# HIVE_BOARD_CLOCK_GEN.net
KiCad netlist of a schematic drawn in Altium Designer
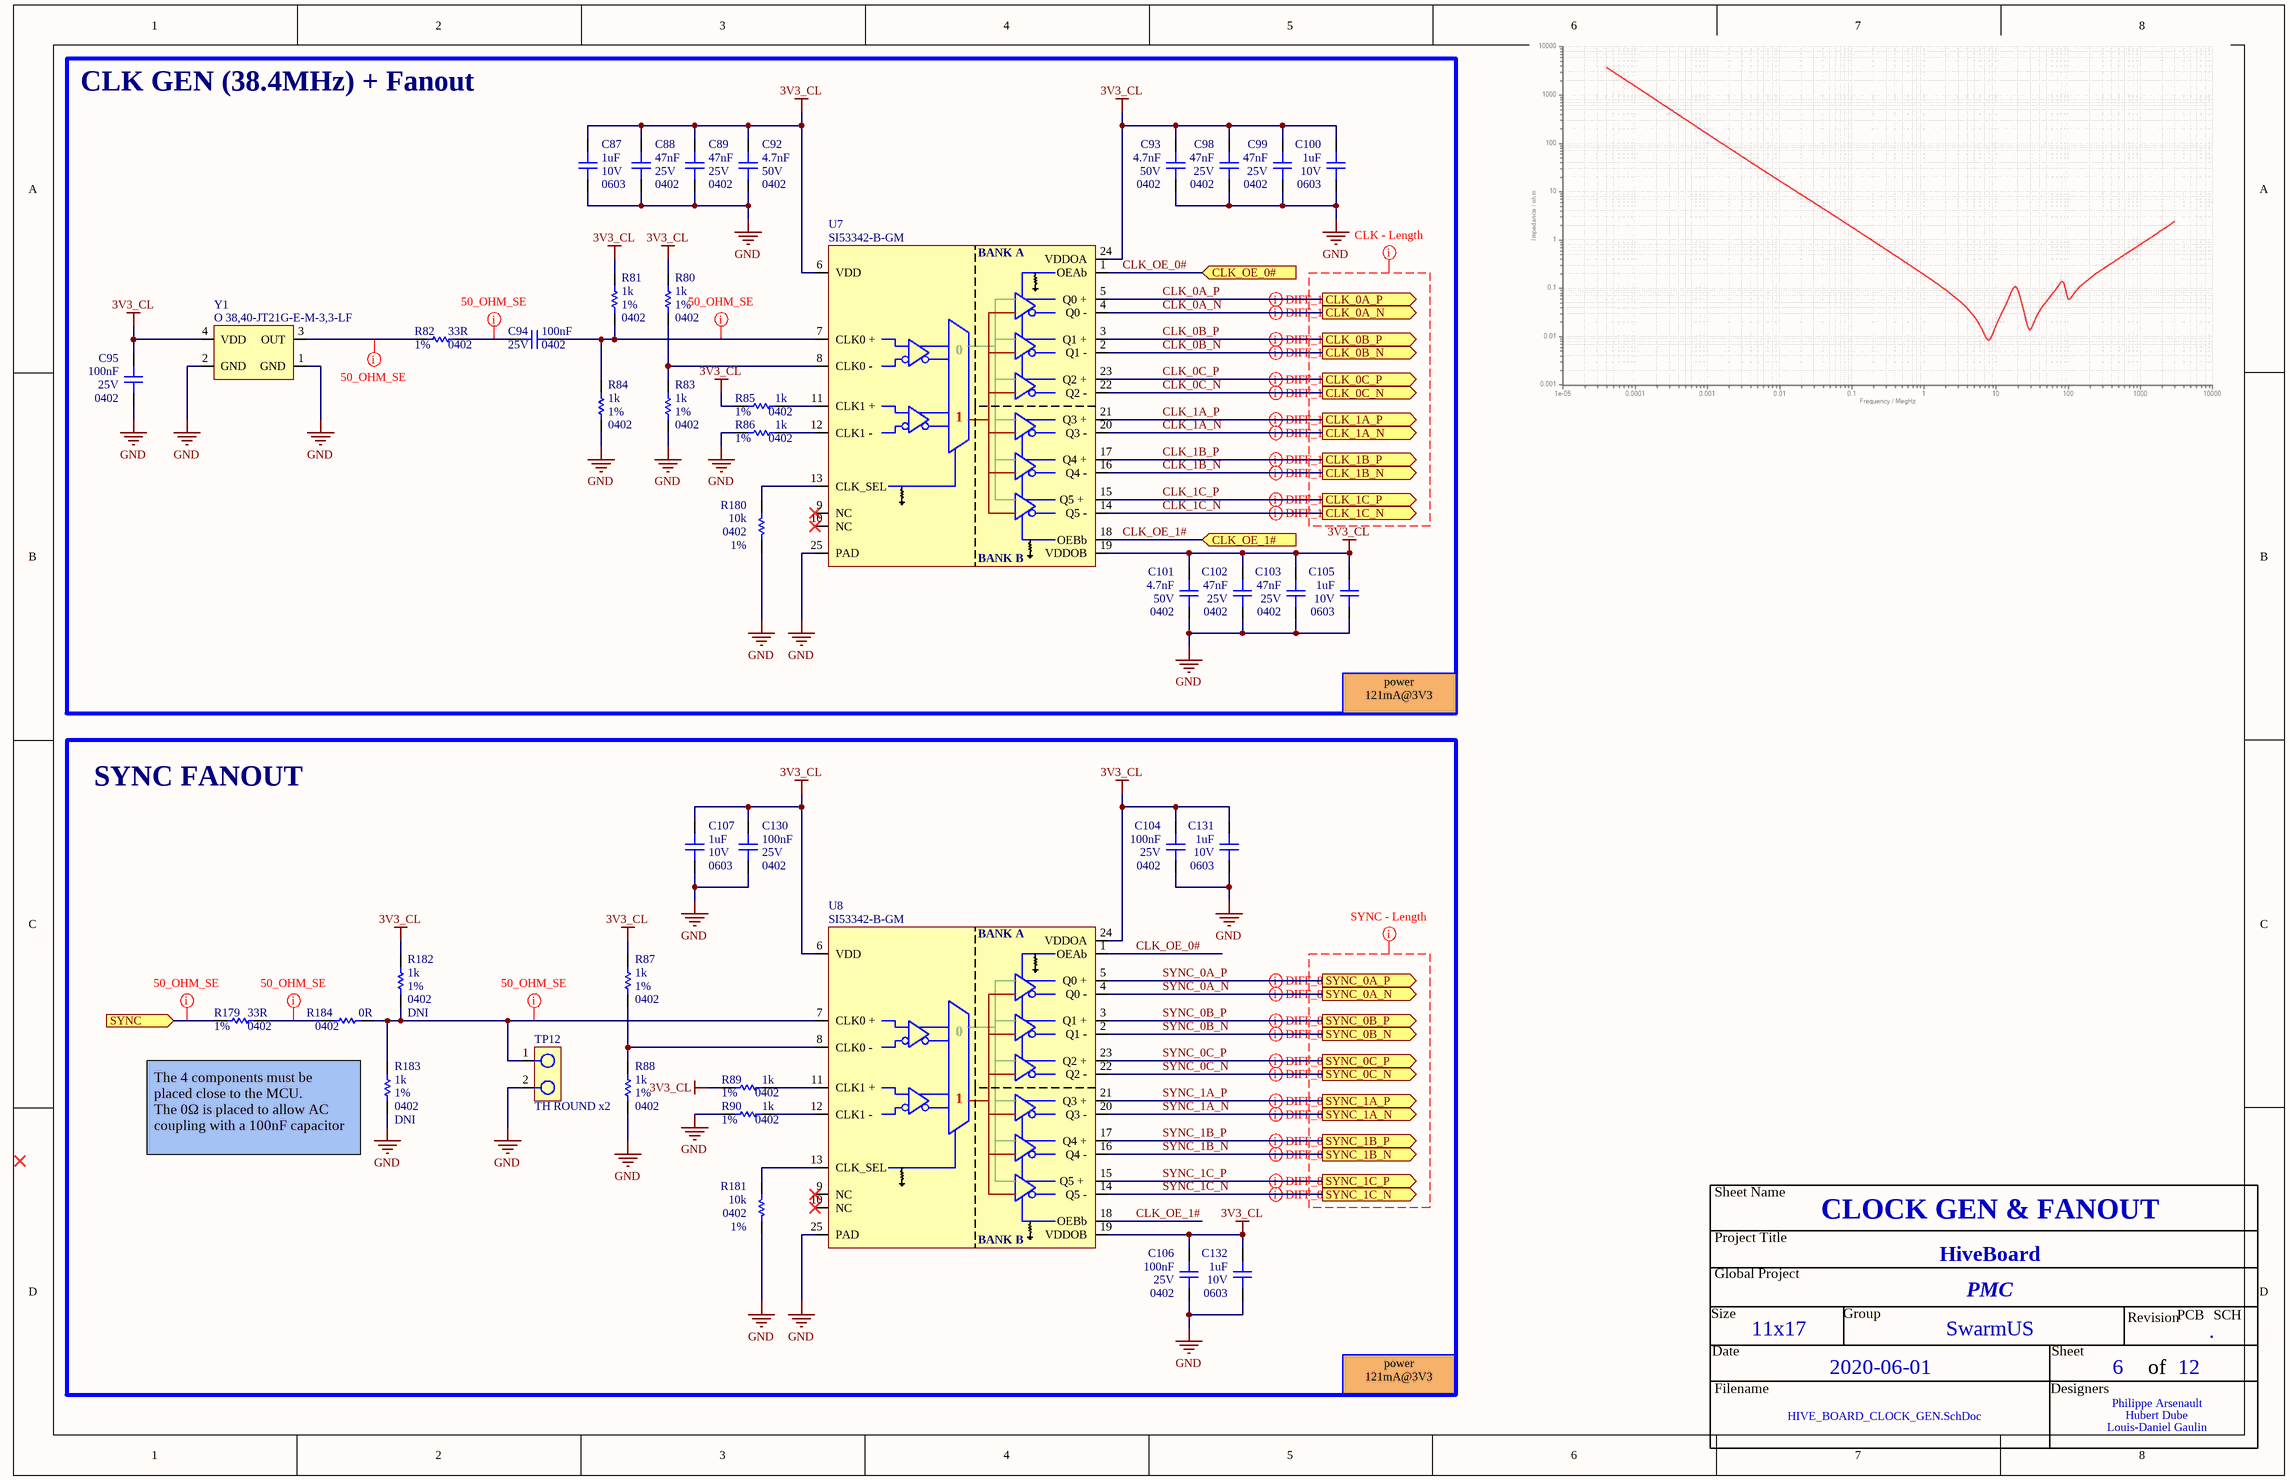
[diagram p0: HIVE_BOARD_CLOCK_GEN.SchDoc]

(export (version "E")
  (design (tool "Eeschema 10.0.6"))
  (components
    (comp (ref "C87")
      (value "1uF")
      (footprint "CAP_CER_0603")
      (description "CAP - CER 1uF 10V 10% X5R - 0603")
      (fields
        (field (name "TOLERANCE") "10%")
        (field (name "PACKAGE") "0603")
        (field (name "VOLTAGE RATING") "10V")
        (field (name "Comment") "C0603C105K8PACTU")
        (field (name "CREATEDBY/DATE") "Hubert Dube - 21/07/20")
        (field (name "VERIFIEDBY") "Louis-Daniel Gaulin - 21/07/20")
      )
      (libsource (lib "SWARMUS_LIB") (part "CAP_CER_C0603C105K8PACTU"))
    )
    (comp (ref "C88")
      (value "47nF")
      (footprint "CAP_CER_0402")
      (description "CAP - CER 47nF 25V X7R - 0402")
      (fields
        (field (name "TOLERANCE") "10%")
        (field (name "PACKAGE") "0402")
        (field (name "VOLTAGE RATING") "25V")
        (field (name "Comment") "GRM155R71E473KA88J")
        (field (name "CREATEDBY/DATE") "P. Marcoux 2020-02-05")
        (field (name "VERIFIEDBY") "C.Paulin - 22/04/2020")
      )
      (libsource (lib "GRAMS_MASTER_LIB") (part "CAP_CER_GRM155R71E473KA88J"))
    )
    (comp (ref "C89")
      (value "47nF")
      (footprint "CAP_CER_0402")
      (description "CAP - CER 47nF 25V X7R - 0402")
      (fields
        (field (name "TOLERANCE") "10%")
        (field (name "PACKAGE") "0402")
        (field (name "VOLTAGE RATING") "25V")
        (field (name "Comment") "GRM155R71E473KA88J")
        (field (name "CREATEDBY/DATE") "P. Marcoux 2020-02-05")
        (field (name "VERIFIEDBY") "C.Paulin - 22/04/2020")
      )
      (libsource (lib "GRAMS_MASTER_LIB") (part "CAP_CER_GRM155R71E473KA88J"))
    )
    (comp (ref "C92")
      (value "4.7nF")
      (footprint "CAP_CER_0402")
      (description "CAP - CER 4700PF 50V X7R 0402")
      (fields
        (field (name "TOLERANCE") "±10%")
        (field (name "PACKAGE") "0402")
        (field (name "VOLTAGE RATING") "50V")
        (field (name "Comment") "CL05B472KB5VPNC")
        (field (name "CREATEDBY/DATE") "Philippe Arsenault/ 2021-03-26")
      )
      (libsource (lib "SWARMUS_LIB") (part "CAP_CER_CL05B472KB5VPNC"))
    )
    (comp (ref "C93")
      (value "4.7nF")
      (footprint "CAP_CER_0402")
      (description "CAP - CER 4700PF 50V X7R 0402")
      (fields
        (field (name "TOLERANCE") "±10%")
        (field (name "PACKAGE") "0402")
        (field (name "VOLTAGE RATING") "50V")
        (field (name "Comment") "CL05B472KB5VPNC")
        (field (name "CREATEDBY/DATE") "Philippe Arsenault/ 2021-03-26")
      )
      (libsource (lib "SWARMUS_LIB") (part "CAP_CER_CL05B472KB5VPNC"))
    )
    (comp (ref "C94")
      (value "100nF")
      (footprint "CAP_CER_0402")
      (description "CAP - CER 0.1µF 10% 25V X7R - 0402")
      (fields
        (field (name "TOLERANCE") "10%")
        (field (name "PACKAGE") "0402")
        (field (name "VOLTAGE RATING") "25V")
        (field (name "Comment") "CGA2B3X7R1E104K050BB")
        (field (name "CREATEDBY/DATE") "Nicolas Roy 2018-11-07")
        (field (name "VERIFIEDBY") "Nicolas V. (2019-01-22)")
      )
      (libsource (lib "GRAMS_MASTER_LIB") (part "CAP_CER_CGA2B3X7R1E104K050BB"))
    )
    (comp (ref "C95")
      (value "100nF")
      (footprint "CAP_CER_0402")
      (description "CAP - CER 0.1µF 10% 25V X7R - 0402")
      (fields
        (field (name "TOLERANCE") "10%")
        (field (name "PACKAGE") "0402")
        (field (name "VOLTAGE RATING") "25V")
        (field (name "Comment") "CGA2B3X7R1E104K050BB")
        (field (name "CREATEDBY/DATE") "Nicolas Roy 2018-11-07")
        (field (name "VERIFIEDBY") "Nicolas V. (2019-01-22)")
      )
      (libsource (lib "GRAMS_MASTER_LIB") (part "CAP_CER_CGA2B3X7R1E104K050BB"))
    )
    (comp (ref "C98")
      (value "47nF")
      (footprint "CAP_CER_0402")
      (description "CAP - CER 47nF 25V X7R - 0402")
      (fields
        (field (name "TOLERANCE") "10%")
        (field (name "PACKAGE") "0402")
        (field (name "VOLTAGE RATING") "25V")
        (field (name "Comment") "GRM155R71E473KA88J")
        (field (name "CREATEDBY/DATE") "P. Marcoux 2020-02-05")
        (field (name "VERIFIEDBY") "C.Paulin - 22/04/2020")
      )
      (libsource (lib "GRAMS_MASTER_LIB") (part "CAP_CER_GRM155R71E473KA88J"))
    )
    (comp (ref "C99")
      (value "47nF")
      (footprint "CAP_CER_0402")
      (description "CAP - CER 47nF 25V X7R - 0402")
      (fields
        (field (name "TOLERANCE") "10%")
        (field (name "PACKAGE") "0402")
        (field (name "VOLTAGE RATING") "25V")
        (field (name "Comment") "GRM155R71E473KA88J")
        (field (name "CREATEDBY/DATE") "P. Marcoux 2020-02-05")
        (field (name "VERIFIEDBY") "C.Paulin - 22/04/2020")
      )
      (libsource (lib "GRAMS_MASTER_LIB") (part "CAP_CER_GRM155R71E473KA88J"))
    )
    (comp (ref "C100")
      (value "1uF")
      (footprint "CAP_CER_0603")
      (description "CAP - CER 1uF 10V 10% X5R - 0603")
      (fields
        (field (name "TOLERANCE") "10%")
        (field (name "PACKAGE") "0603")
        (field (name "VOLTAGE RATING") "10V")
        (field (name "Comment") "C0603C105K8PACTU")
        (field (name "CREATEDBY/DATE") "Hubert Dube - 21/07/20")
        (field (name "VERIFIEDBY") "Louis-Daniel Gaulin - 21/07/20")
      )
      (libsource (lib "SWARMUS_LIB") (part "CAP_CER_C0603C105K8PACTU"))
    )
    (comp (ref "C101")
      (value "4.7nF")
      (footprint "CAP_CER_0402")
      (description "CAP - CER 4700PF 50V X7R 0402")
      (fields
        (field (name "TOLERANCE") "±10%")
        (field (name "PACKAGE") "0402")
        (field (name "VOLTAGE RATING") "50V")
        (field (name "Comment") "CL05B472KB5VPNC")
        (field (name "CREATEDBY/DATE") "Philippe Arsenault/ 2021-03-26")
      )
      (libsource (lib "SWARMUS_LIB") (part "CAP_CER_CL05B472KB5VPNC"))
    )
    (comp (ref "C102")
      (value "47nF")
      (footprint "CAP_CER_0402")
      (description "CAP - CER 47nF 25V X7R - 0402")
      (fields
        (field (name "TOLERANCE") "10%")
        (field (name "PACKAGE") "0402")
        (field (name "VOLTAGE RATING") "25V")
        (field (name "Comment") "GRM155R71E473KA88J")
        (field (name "CREATEDBY/DATE") "P. Marcoux 2020-02-05")
        (field (name "VERIFIEDBY") "C.Paulin - 22/04/2020")
      )
      (libsource (lib "GRAMS_MASTER_LIB") (part "CAP_CER_GRM155R71E473KA88J"))
    )
    (comp (ref "C103")
      (value "47nF")
      (footprint "CAP_CER_0402")
      (description "CAP - CER 47nF 25V X7R - 0402")
      (fields
        (field (name "TOLERANCE") "10%")
        (field (name "PACKAGE") "0402")
        (field (name "VOLTAGE RATING") "25V")
        (field (name "Comment") "GRM155R71E473KA88J")
        (field (name "CREATEDBY/DATE") "P. Marcoux 2020-02-05")
        (field (name "VERIFIEDBY") "C.Paulin - 22/04/2020")
      )
      (libsource (lib "GRAMS_MASTER_LIB") (part "CAP_CER_GRM155R71E473KA88J"))
    )
    (comp (ref "C104")
      (value "100nF")
      (footprint "CAP_CER_0402")
      (description "CAP - CER 0.1µF 10% 25V X7R - 0402")
      (fields
        (field (name "TOLERANCE") "10%")
        (field (name "PACKAGE") "0402")
        (field (name "VOLTAGE RATING") "25V")
        (field (name "Comment") "CGA2B3X7R1E104K050BB")
        (field (name "CREATEDBY/DATE") "Nicolas Roy 2018-11-07")
        (field (name "VERIFIEDBY") "Nicolas V. (2019-01-22)")
      )
      (libsource (lib "GRAMS_MASTER_LIB") (part "CAP_CER_CGA2B3X7R1E104K050BB"))
    )
    (comp (ref "C105")
      (value "1uF")
      (footprint "CAP_CER_0603")
      (description "CAP - CER 1uF 10V 10% X5R - 0603")
      (fields
        (field (name "TOLERANCE") "10%")
        (field (name "PACKAGE") "0603")
        (field (name "VOLTAGE RATING") "10V")
        (field (name "Comment") "C0603C105K8PACTU")
        (field (name "CREATEDBY/DATE") "Hubert Dube - 21/07/20")
        (field (name "VERIFIEDBY") "Louis-Daniel Gaulin - 21/07/20")
      )
      (libsource (lib "SWARMUS_LIB") (part "CAP_CER_C0603C105K8PACTU"))
    )
    (comp (ref "C106")
      (value "100nF")
      (footprint "CAP_CER_0402")
      (description "CAP - CER 0.1µF 10% 25V X7R - 0402")
      (fields
        (field (name "TOLERANCE") "10%")
        (field (name "PACKAGE") "0402")
        (field (name "VOLTAGE RATING") "25V")
        (field (name "Comment") "CGA2B3X7R1E104K050BB")
        (field (name "CREATEDBY/DATE") "Nicolas Roy 2018-11-07")
        (field (name "VERIFIEDBY") "Nicolas V. (2019-01-22)")
      )
      (libsource (lib "GRAMS_MASTER_LIB") (part "CAP_CER_CGA2B3X7R1E104K050BB"))
    )
    (comp (ref "C107")
      (value "1uF")
      (footprint "CAP_CER_0603")
      (description "CAP - CER 1uF 10V 10% X5R - 0603")
      (fields
        (field (name "TOLERANCE") "10%")
        (field (name "PACKAGE") "0603")
        (field (name "VOLTAGE RATING") "10V")
        (field (name "Comment") "C0603C105K8PACTU")
        (field (name "CREATEDBY/DATE") "Hubert Dube - 21/07/20")
        (field (name "VERIFIEDBY") "Louis-Daniel Gaulin - 21/07/20")
      )
      (libsource (lib "SWARMUS_LIB") (part "CAP_CER_C0603C105K8PACTU"))
    )
    (comp (ref "C130")
      (value "100nF")
      (footprint "CAP_CER_0402")
      (description "CAP - CER 0.1µF 10% 25V X7R - 0402")
      (fields
        (field (name "TOLERANCE") "10%")
        (field (name "PACKAGE") "0402")
        (field (name "VOLTAGE RATING") "25V")
        (field (name "Comment") "CGA2B3X7R1E104K050BB")
        (field (name "CREATEDBY/DATE") "Nicolas Roy 2018-11-07")
        (field (name "VERIFIEDBY") "Nicolas V. (2019-01-22)")
      )
      (libsource (lib "GRAMS_MASTER_LIB") (part "CAP_CER_CGA2B3X7R1E104K050BB"))
    )
    (comp (ref "C131")
      (value "1uF")
      (footprint "CAP_CER_0603")
      (description "CAP - CER 1uF 10V 10% X5R - 0603")
      (fields
        (field (name "TOLERANCE") "10%")
        (field (name "PACKAGE") "0603")
        (field (name "VOLTAGE RATING") "10V")
        (field (name "Comment") "C0603C105K8PACTU")
        (field (name "CREATEDBY/DATE") "Hubert Dube - 21/07/20")
        (field (name "VERIFIEDBY") "Louis-Daniel Gaulin - 21/07/20")
      )
      (libsource (lib "SWARMUS_LIB") (part "CAP_CER_C0603C105K8PACTU"))
    )
    (comp (ref "C132")
      (value "1uF")
      (footprint "CAP_CER_0603")
      (description "CAP - CER 1uF 10V 10% X5R - 0603")
      (fields
        (field (name "TOLERANCE") "10%")
        (field (name "PACKAGE") "0603")
        (field (name "VOLTAGE RATING") "10V")
        (field (name "Comment") "C0603C105K8PACTU")
        (field (name "CREATEDBY/DATE") "Hubert Dube - 21/07/20")
        (field (name "VERIFIEDBY") "Louis-Daniel Gaulin - 21/07/20")
      )
      (libsource (lib "SWARMUS_LIB") (part "CAP_CER_C0603C105K8PACTU"))
    )
    (comp (ref "R80")
      (value "1k")
      (footprint "RES_0402")
      (description "RES - 1K OHM 1% 1/16W - 0402")
      (fields
        (field (name "TOLERANCE") "1%")
        (field (name "PACKAGE") "0402")
        (field (name "Comment") "RC0402FR-071KL")
        (field (name "CREATEDBY/DATE") "Jonathan Bouchard 2018-07-05")
        (field (name "VERIFIEDBY") "Arnaud Samson 16-07-18")
      )
      (libsource (lib "GRAMS_MASTER_LIB") (part "RES_RC0402FR-071KL"))
    )
    (comp (ref "R81")
      (value "1k")
      (footprint "RES_0402")
      (description "RES - 1K OHM 1% 1/16W - 0402")
      (fields
        (field (name "TOLERANCE") "1%")
        (field (name "PACKAGE") "0402")
        (field (name "Comment") "RC0402FR-071KL")
        (field (name "CREATEDBY/DATE") "Jonathan Bouchard 2018-07-05")
        (field (name "VERIFIEDBY") "Arnaud Samson 16-07-18")
      )
      (libsource (lib "GRAMS_MASTER_LIB") (part "RES_RC0402FR-071KL"))
    )
    (comp (ref "R82")
      (value "33R")
      (footprint "RES_0402")
      (description "RES - 33 OHM 1% 1/16W - 0402")
      (fields
        (field (name "TOLERANCE") "1%")
        (field (name "PACKAGE") "0402")
        (field (name "Comment") "RC0402FR-0733RL")
        (field (name "CREATEDBY/DATE") "Louis-Daniel Gaulin/ 14/01/2020")
        (field (name "VERIFIEDBY") "C.Paulin - 21/01/2020")
      )
      (libsource (lib "GRAMS_MASTER_LIB") (part "RES_RC0402FR-0733RL"))
    )
    (comp (ref "R83")
      (value "1k")
      (footprint "RES_0402")
      (description "RES - 1K OHM 1% 1/16W - 0402")
      (fields
        (field (name "TOLERANCE") "1%")
        (field (name "PACKAGE") "0402")
        (field (name "Comment") "RC0402FR-071KL")
        (field (name "CREATEDBY/DATE") "Jonathan Bouchard 2018-07-05")
        (field (name "VERIFIEDBY") "Arnaud Samson 16-07-18")
      )
      (libsource (lib "GRAMS_MASTER_LIB") (part "RES_RC0402FR-071KL"))
    )
    (comp (ref "R84")
      (value "1k")
      (footprint "RES_0402")
      (description "RES - 1K OHM 1% 1/16W - 0402")
      (fields
        (field (name "TOLERANCE") "1%")
        (field (name "PACKAGE") "0402")
        (field (name "Comment") "RC0402FR-071KL")
        (field (name "CREATEDBY/DATE") "Jonathan Bouchard 2018-07-05")
        (field (name "VERIFIEDBY") "Arnaud Samson 16-07-18")
      )
      (libsource (lib "GRAMS_MASTER_LIB") (part "RES_RC0402FR-071KL"))
    )
    (comp (ref "R85")
      (value "1k")
      (footprint "RES_0402")
      (description "RES - 1K OHM 1% 1/16W - 0402")
      (fields
        (field (name "TOLERANCE") "1%")
        (field (name "PACKAGE") "0402")
        (field (name "Comment") "RC0402FR-071KL")
        (field (name "CREATEDBY/DATE") "Jonathan Bouchard 2018-07-05")
        (field (name "VERIFIEDBY") "Arnaud Samson 16-07-18")
      )
      (libsource (lib "GRAMS_MASTER_LIB") (part "RES_RC0402FR-071KL"))
    )
    (comp (ref "R86")
      (value "1k")
      (footprint "RES_0402")
      (description "RES - 1K OHM 1% 1/16W - 0402")
      (fields
        (field (name "TOLERANCE") "1%")
        (field (name "PACKAGE") "0402")
        (field (name "Comment") "RC0402FR-071KL")
        (field (name "CREATEDBY/DATE") "Jonathan Bouchard 2018-07-05")
        (field (name "VERIFIEDBY") "Arnaud Samson 16-07-18")
      )
      (libsource (lib "GRAMS_MASTER_LIB") (part "RES_RC0402FR-071KL"))
    )
    (comp (ref "R87")
      (value "1k")
      (footprint "RES_0402")
      (description "RES - 1K OHM 1% 1/16W - 0402")
      (fields
        (field (name "TOLERANCE") "1%")
        (field (name "PACKAGE") "0402")
        (field (name "Comment") "RC0402FR-071KL")
        (field (name "CREATEDBY/DATE") "Jonathan Bouchard 2018-07-05")
        (field (name "VERIFIEDBY") "Arnaud Samson 16-07-18")
      )
      (libsource (lib "GRAMS_MASTER_LIB") (part "RES_RC0402FR-071KL"))
    )
    (comp (ref "R88")
      (value "1k")
      (footprint "RES_0402")
      (description "RES - 1K OHM 1% 1/16W - 0402")
      (fields
        (field (name "TOLERANCE") "1%")
        (field (name "PACKAGE") "0402")
        (field (name "Comment") "RC0402FR-071KL")
        (field (name "CREATEDBY/DATE") "Jonathan Bouchard 2018-07-05")
        (field (name "VERIFIEDBY") "Arnaud Samson 16-07-18")
      )
      (libsource (lib "GRAMS_MASTER_LIB") (part "RES_RC0402FR-071KL"))
    )
    (comp (ref "R89")
      (value "1k")
      (footprint "RES_0402")
      (description "RES - 1K OHM 1% 1/16W - 0402")
      (fields
        (field (name "TOLERANCE") "1%")
        (field (name "PACKAGE") "0402")
        (field (name "Comment") "RC0402FR-071KL")
        (field (name "CREATEDBY/DATE") "Jonathan Bouchard 2018-07-05")
        (field (name "VERIFIEDBY") "Arnaud Samson 16-07-18")
      )
      (libsource (lib "GRAMS_MASTER_LIB") (part "RES_RC0402FR-071KL"))
    )
    (comp (ref "R90")
      (value "1k")
      (footprint "RES_0402")
      (description "RES - 1K OHM 1% 1/16W - 0402")
      (fields
        (field (name "TOLERANCE") "1%")
        (field (name "PACKAGE") "0402")
        (field (name "Comment") "RC0402FR-071KL")
        (field (name "CREATEDBY/DATE") "Jonathan Bouchard 2018-07-05")
        (field (name "VERIFIEDBY") "Arnaud Samson 16-07-18")
      )
      (libsource (lib "GRAMS_MASTER_LIB") (part "RES_RC0402FR-071KL"))
    )
    (comp (ref "R179")
      (value "33R")
      (footprint "RES_0402")
      (description "RES - 33 OHM 1% 1/16W - 0402")
      (fields
        (field (name "TOLERANCE") "1%")
        (field (name "PACKAGE") "0402")
        (field (name "Comment") "RC0402FR-0733RL")
        (field (name "CREATEDBY/DATE") "Louis-Daniel Gaulin/ 14/01/2020")
        (field (name "VERIFIEDBY") "C.Paulin - 21/01/2020")
      )
      (libsource (lib "GRAMS_MASTER_LIB") (part "RES_RC0402FR-0733RL"))
    )
    (comp (ref "R180")
      (value "10k")
      (footprint "RES_0402")
      (description "RES - 10K OHMS 1% 1/16W - 0402")
      (fields
        (field (name "TOLERANCE") "1%")
        (field (name "PACKAGE") "0402")
        (field (name "Comment") "RC0402FR-0710KL")
        (field (name "CREATEDBY/DATE") "Nicolas V. (2018-11-20)")
        (field (name "VERIFIEDBY") "Nicolas V. (2018-11-20)")
      )
      (libsource (lib "GRAMS_MASTER_LIB") (part "RES_RC0402FR-0710KL"))
    )
    (comp (ref "R181")
      (value "10k")
      (footprint "RES_0402")
      (description "RES - 10K OHMS 1% 1/16W - 0402")
      (fields
        (field (name "TOLERANCE") "1%")
        (field (name "PACKAGE") "0402")
        (field (name "Comment") "RC0402FR-0710KL")
        (field (name "CREATEDBY/DATE") "Nicolas V. (2018-11-20)")
        (field (name "VERIFIEDBY") "Nicolas V. (2018-11-20)")
      )
      (libsource (lib "GRAMS_MASTER_LIB") (part "RES_RC0402FR-0710KL"))
    )
    (comp (ref "R182")
      (value "1k")
      (footprint "RES_0402")
      (description "RES - 1K OHM 1% 1/16W - 0402")
      (fields
        (field (name "TOLERANCE") "1%")
        (field (name "ASSEMBLY NOTE") "DNI")
        (field (name "PACKAGE") "0402")
        (field (name "Comment") "RC0402FR-071KL")
        (field (name "CREATEDBY/DATE") "Jonathan Bouchard 2018-07-05")
        (field (name "VERIFIEDBY") "Arnaud Samson 16-07-18")
      )
      (libsource (lib "GRAMS_MASTER_LIB") (part "RES_RC0402FR-071KL"))
    )
    (comp (ref "R183")
      (value "1k")
      (footprint "RES_0402")
      (description "RES - 1K OHM 1% 1/16W - 0402")
      (fields
        (field (name "TOLERANCE") "1%")
        (field (name "ASSEMBLY NOTE") "DNI")
        (field (name "PACKAGE") "0402")
        (field (name "Comment") "RC0402FR-071KL")
        (field (name "CREATEDBY/DATE") "Jonathan Bouchard 2018-07-05")
        (field (name "VERIFIEDBY") "Arnaud Samson 16-07-18")
      )
      (libsource (lib "GRAMS_MASTER_LIB") (part "RES_RC0402FR-071KL"))
    )
    (comp (ref "R184")
      (value "0R")
      (footprint "RES_0402")
      (description "RES - 0R 1/16W 1A  - 0402")
      (fields
        (field (name "PACKAGE") "0402")
        (field (name "Comment") "RC0402FR-070RL")
        (field (name "CREATEDBY/DATE") "Keven Deslandes 2018-09-12")
        (field (name "VERIFIEDBY") "Caroline Paulin - 27 fév 2019")
      )
      (libsource (lib "GRAMS_MASTER_LIB") (part "RES_RC0402FR-070RL"))
    )
    (comp (ref "TP12")
      (value "TH ROUND x2")
      (footprint "TPO_TH_ROUND_0.7mm_DOUBLE")
      (description "TPO - TH round 0.7mm double - 2-SMD")
      (fields
        (field (name "CREATEDBY/DATE") "Philippe Arsenault / 20-04-2021")
        (field (name "VERIFIEDBY") "Louis-Daniel Gaulin / 29-04-2021")
      )
      (libsource (lib "SWARMUS_LIB") (part "TPO_TH_ROUND_0.7mm_DOUBLE"))
    )
    (comp (ref "U7")
      (value "SI53342-B-GM")
      (footprint "TIM_FAN_SI53342-B-GM")
      (description "TIM_FAN -  Clock Fanout Buffer 1.25GHz , Multiplexer IC 2:6 - 24-VFQFN EP")
      (fields (field (name "CREATEDBY/DATE") "Philippe Arsenault/ 2021-04-01"))
      (libsource (lib "SWARMUS_LIB") (part "TIM_FAN_SI53342-B-GM"))
    )
    (comp (ref "U8")
      (value "SI53342-B-GM")
      (footprint "TIM_FAN_SI53342-B-GM")
      (description "TIM_FAN -  Clock Fanout Buffer 1.25GHz , Multiplexer IC 2:6 - 24-VFQFN EP")
      (fields (field (name "CREATEDBY/DATE") "Philippe Arsenault/ 2021-04-01"))
      (libsource (lib "SWARMUS_LIB") (part "TIM_FAN_SI53342-B-GM"))
    )
    (comp (ref "Y1")
      (value "O 38,40-JT21G-E-M-3,3-LF")
      (footprint "OSC_O 38,40-JT21G-E-M-3,3-LF")
      (description "OSC -  TCXO Clipped Sine Wave Oscillator 3.3V 38.4MHz - 4-SMD")
      (fields
        (field (name "TOLERANCE") "±2 ppm")
        (field (name "CREATEDBY/DATE") "Louis-Daniel Gaulin / 30-04-2021")
        (field (name "VERIFIEDBY") "Philippe Arsenault/2021-04-30")
      )
      (libsource (lib "SWARMUS_LIB") (part "OSC_O 38,40-JT21G-E-M-3,3-LF"))
    )
  )
  (nets
    (net (code "1") (name "/CLK_0A_N") (class "Default")
      (node (ref "U7") (pin "4") (pinfunction "Q0_-_4") (pintype "passive"))
    )
    (net (code "2") (name "/CLK_0A_P") (class "Default")
      (node (ref "U7") (pin "5") (pinfunction "Q0_+_5") (pintype "passive"))
    )
    (net (code "3") (name "/CLK_0B_N") (class "Default")
      (node (ref "U7") (pin "2") (pinfunction "Q1_-_2") (pintype "passive"))
    )
    (net (code "4") (name "/CLK_0B_P") (class "Default")
      (node (ref "U7") (pin "3") (pinfunction "Q1_+_3") (pintype "passive"))
    )
    (net (code "5") (name "/CLK_0C_N") (class "Default")
      (node (ref "U7") (pin "22") (pinfunction "Q2_-_22") (pintype "passive"))
    )
    (net (code "6") (name "/CLK_0C_P") (class "Default")
      (node (ref "U7") (pin "23") (pinfunction "Q2_+_23") (pintype "passive"))
    )
    (net (code "7") (name "/CLK_1A_N") (class "Default")
      (node (ref "U7") (pin "20") (pinfunction "Q3_-_20") (pintype "passive"))
    )
    (net (code "8") (name "/CLK_1A_P") (class "Default")
      (node (ref "U7") (pin "21") (pinfunction "Q3_+_21") (pintype "passive"))
    )
    (net (code "9") (name "/CLK_1B_N") (class "Default")
      (node (ref "U7") (pin "16") (pinfunction "Q4_-_16") (pintype "passive"))
    )
    (net (code "10") (name "/CLK_1B_P") (class "Default")
      (node (ref "U7") (pin "17") (pinfunction "Q4_+_17") (pintype "passive"))
    )
    (net (code "11") (name "/CLK_1C_N") (class "Default")
      (node (ref "U7") (pin "14") (pinfunction "Q5_-_14") (pintype "passive"))
    )
    (net (code "12") (name "/CLK_1C_P") (class "Default")
      (node (ref "U7") (pin "15") (pinfunction "Q5_+_15") (pintype "passive"))
    )
    (net (code "13") (name "/CLK_OE_0#") (class "Default")
      (node (ref "U7") (pin "1") (pinfunction "OEAb_1") (pintype "passive"))
      (node (ref "U8") (pin "1") (pinfunction "OEAb_1") (pintype "passive"))
    )
    (net (code "14") (name "/CLK_OE_1#") (class "Default")
      (node (ref "U7") (pin "18") (pinfunction "OEBb_18") (pintype "passive"))
      (node (ref "U8") (pin "18") (pinfunction "OEBb_18") (pintype "passive"))
    )
    (net (code "15") (name "/SYNC") (class "Default")
      (node (ref "R179") (pin "2") (pinfunction "2_2") (pintype "passive"))
    )
    (net (code "16") (name "/SYNC_0A_N") (class "Default")
      (node (ref "U8") (pin "4") (pinfunction "Q0_-_4") (pintype "passive"))
    )
    (net (code "17") (name "/SYNC_0A_P") (class "Default")
      (node (ref "U8") (pin "5") (pinfunction "Q0_+_5") (pintype "passive"))
    )
    (net (code "18") (name "/SYNC_0B_N") (class "Default")
      (node (ref "U8") (pin "2") (pinfunction "Q1_-_2") (pintype "passive"))
    )
    (net (code "19") (name "/SYNC_0B_P") (class "Default")
      (node (ref "U8") (pin "3") (pinfunction "Q1_+_3") (pintype "passive"))
    )
    (net (code "20") (name "/SYNC_0C_N") (class "Default")
      (node (ref "U8") (pin "22") (pinfunction "Q2_-_22") (pintype "passive"))
    )
    (net (code "21") (name "/SYNC_0C_P") (class "Default")
      (node (ref "U8") (pin "23") (pinfunction "Q2_+_23") (pintype "passive"))
    )
    (net (code "22") (name "/SYNC_1A_N") (class "Default")
      (node (ref "U8") (pin "20") (pinfunction "Q3_-_20") (pintype "passive"))
    )
    (net (code "23") (name "/SYNC_1A_P") (class "Default")
      (node (ref "U8") (pin "21") (pinfunction "Q3_+_21") (pintype "passive"))
    )
    (net (code "24") (name "/SYNC_1B_N") (class "Default")
      (node (ref "U8") (pin "16") (pinfunction "Q4_-_16") (pintype "passive"))
    )
    (net (code "25") (name "/SYNC_1B_P") (class "Default")
      (node (ref "U8") (pin "17") (pinfunction "Q4_+_17") (pintype "passive"))
    )
    (net (code "26") (name "/SYNC_1C_N") (class "Default")
      (node (ref "U8") (pin "14") (pinfunction "Q5_-_14") (pintype "passive"))
    )
    (net (code "27") (name "/SYNC_1C_P") (class "Default")
      (node (ref "U8") (pin "15") (pinfunction "Q5_+_15") (pintype "passive"))
    )
    (net (code "28") (name "3V3_CL") (class "Default")
      (node (ref "C100") (pin "1") (pinfunction "1_1") (pintype "passive"))
      (node (ref "C101") (pin "2") (pinfunction "2_2") (pintype "passive"))
      (node (ref "C102") (pin "2") (pinfunction "2_2") (pintype "passive"))
      (node (ref "C103") (pin "2") (pinfunction "2_2") (pintype "passive"))
      (node (ref "C104") (pin "2") (pinfunction "2_2") (pintype "passive"))
      (node (ref "C105") (pin "1") (pinfunction "1_1") (pintype "passive"))
      (node (ref "C106") (pin "2") (pinfunction "2_2") (pintype "passive"))
      (node (ref "C107") (pin "1") (pinfunction "1_1") (pintype "passive"))
      (node (ref "C130") (pin "2") (pinfunction "2_2") (pintype "passive"))
      (node (ref "C131") (pin "1") (pinfunction "1_1") (pintype "passive"))
      (node (ref "C132") (pin "1") (pinfunction "1_1") (pintype "passive"))
      (node (ref "C87") (pin "1") (pinfunction "1_1") (pintype "passive"))
      (node (ref "C88") (pin "2") (pinfunction "2_2") (pintype "passive"))
      (node (ref "C89") (pin "2") (pinfunction "2_2") (pintype "passive"))
      (node (ref "C92") (pin "2") (pinfunction "2_2") (pintype "passive"))
      (node (ref "C93") (pin "2") (pinfunction "2_2") (pintype "passive"))
      (node (ref "C95") (pin "2") (pinfunction "2_2") (pintype "passive"))
      (node (ref "C98") (pin "2") (pinfunction "2_2") (pintype "passive"))
      (node (ref "C99") (pin "2") (pinfunction "2_2") (pintype "passive"))
      (node (ref "R182") (pin "2") (pinfunction "2_2") (pintype "passive"))
      (node (ref "R80") (pin "2") (pinfunction "2_2") (pintype "passive"))
      (node (ref "R81") (pin "2") (pinfunction "2_2") (pintype "passive"))
      (node (ref "R85") (pin "2") (pinfunction "2_2") (pintype "passive"))
      (node (ref "R87") (pin "2") (pinfunction "2_2") (pintype "passive"))
      (node (ref "R89") (pin "2") (pinfunction "2_2") (pintype "passive"))
      (node (ref "U7") (pin "19") (pinfunction "VDDOB_19") (pintype "passive"))
      (node (ref "U7") (pin "24") (pinfunction "VDDOA_24") (pintype "passive"))
      (node (ref "U7") (pin "6") (pinfunction "VDD_6") (pintype "passive"))
      (node (ref "U8") (pin "19") (pinfunction "VDDOB_19") (pintype "passive"))
      (node (ref "U8") (pin "24") (pinfunction "VDDOA_24") (pintype "passive"))
      (node (ref "U8") (pin "6") (pinfunction "VDD_6") (pintype "passive"))
      (node (ref "Y1") (pin "4") (pinfunction "VDD_4") (pintype "passive"))
    )
    (net (code "29") (name "GND") (class "Default")
      (node (ref "C100") (pin "2") (pinfunction "2_2") (pintype "passive"))
      (node (ref "C101") (pin "1") (pinfunction "1_1") (pintype "passive"))
      (node (ref "C102") (pin "1") (pinfunction "1_1") (pintype "passive"))
      (node (ref "C103") (pin "1") (pinfunction "1_1") (pintype "passive"))
      (node (ref "C104") (pin "1") (pinfunction "1_1") (pintype "passive"))
      (node (ref "C105") (pin "2") (pinfunction "2_2") (pintype "passive"))
      (node (ref "C106") (pin "1") (pinfunction "1_1") (pintype "passive"))
      (node (ref "C107") (pin "2") (pinfunction "2_2") (pintype "passive"))
      (node (ref "C130") (pin "1") (pinfunction "1_1") (pintype "passive"))
      (node (ref "C131") (pin "2") (pinfunction "2_2") (pintype "passive"))
      (node (ref "C132") (pin "2") (pinfunction "2_2") (pintype "passive"))
      (node (ref "C87") (pin "2") (pinfunction "2_2") (pintype "passive"))
      (node (ref "C88") (pin "1") (pinfunction "1_1") (pintype "passive"))
      (node (ref "C89") (pin "1") (pinfunction "1_1") (pintype "passive"))
      (node (ref "C92") (pin "1") (pinfunction "1_1") (pintype "passive"))
      (node (ref "C93") (pin "1") (pinfunction "1_1") (pintype "passive"))
      (node (ref "C95") (pin "1") (pinfunction "1_1") (pintype "passive"))
      (node (ref "C98") (pin "1") (pinfunction "1_1") (pintype "passive"))
      (node (ref "C99") (pin "1") (pinfunction "1_1") (pintype "passive"))
      (node (ref "R180") (pin "2") (pinfunction "2_2") (pintype "passive"))
      (node (ref "R181") (pin "2") (pinfunction "2_2") (pintype "passive"))
      (node (ref "R183") (pin "1") (pinfunction "1_1") (pintype "passive"))
      (node (ref "R83") (pin "1") (pinfunction "1_1") (pintype "passive"))
      (node (ref "R84") (pin "1") (pinfunction "1_1") (pintype "passive"))
      (node (ref "R86") (pin "2") (pinfunction "2_2") (pintype "passive"))
      (node (ref "R88") (pin "1") (pinfunction "1_1") (pintype "passive"))
      (node (ref "R90") (pin "2") (pinfunction "2_2") (pintype "passive"))
      (node (ref "TP12") (pin "2") (pinfunction "2_2") (pintype "passive"))
      (node (ref "U7") (pin "25") (pinfunction "PAD_25") (pintype "passive"))
      (node (ref "U8") (pin "25") (pinfunction "PAD_25") (pintype "passive"))
      (node (ref "Y1") (pin "1") (pinfunction "GND_1") (pintype "passive"))
      (node (ref "Y1") (pin "2") (pinfunction "GND_2") (pintype "passive"))
    )
    (net (code "30") (name "Net-(C94-Pad2)") (class "Default")
      (node (ref "C94") (pin "2") (pinfunction "2_2") (pintype "passive"))
      (node (ref "R82") (pin "1") (pinfunction "1_1") (pintype "passive"))
    )
    (net (code "31") (name "Net-(R179-Pad1)") (class "Default")
      (node (ref "R179") (pin "1") (pinfunction "1_1") (pintype "passive"))
      (node (ref "R184") (pin "2") (pinfunction "2_2") (pintype "passive"))
    )
    (net (code "32") (name "Net-(U7-CLK0_+)") (class "Default")
      (node (ref "C94") (pin "1") (pinfunction "1_1") (pintype "passive"))
      (node (ref "R81") (pin "1") (pinfunction "1_1") (pintype "passive"))
      (node (ref "R84") (pin "2") (pinfunction "2_2") (pintype "passive"))
      (node (ref "U7") (pin "7") (pinfunction "CLK0_+_7") (pintype "passive"))
    )
    (net (code "33") (name "Net-(U7-CLK0_-)") (class "Default")
      (node (ref "R80") (pin "1") (pinfunction "1_1") (pintype "passive"))
      (node (ref "R83") (pin "2") (pinfunction "2_2") (pintype "passive"))
      (node (ref "U7") (pin "8") (pinfunction "CLK0_-_8") (pintype "passive"))
    )
    (net (code "34") (name "Net-(U7-CLK1_+)") (class "Default")
      (node (ref "R85") (pin "1") (pinfunction "1_1") (pintype "passive"))
      (node (ref "U7") (pin "11") (pinfunction "CLK1_+_11") (pintype "passive"))
    )
    (net (code "35") (name "Net-(U7-CLK1_-)") (class "Default")
      (node (ref "R86") (pin "1") (pinfunction "1_1") (pintype "passive"))
      (node (ref "U7") (pin "12") (pinfunction "CLK1_-_12") (pintype "passive"))
    )
    (net (code "36") (name "Net-(U7-CLK_SEL)") (class "Default")
      (node (ref "R180") (pin "1") (pinfunction "1_1") (pintype "passive"))
      (node (ref "U7") (pin "13") (pinfunction "CLK_SEL_13") (pintype "passive"))
    )
    (net (code "37") (name "Net-(U8-CLK0_+)") (class "Default")
      (node (ref "R182") (pin "1") (pinfunction "1_1") (pintype "passive"))
      (node (ref "R183") (pin "2") (pinfunction "2_2") (pintype "passive"))
      (node (ref "R184") (pin "1") (pinfunction "1_1") (pintype "passive"))
      (node (ref "TP12") (pin "1") (pinfunction "1_1") (pintype "passive"))
      (node (ref "U8") (pin "7") (pinfunction "CLK0_+_7") (pintype "passive"))
    )
    (net (code "38") (name "Net-(U8-CLK0_-)") (class "Default")
      (node (ref "R87") (pin "1") (pinfunction "1_1") (pintype "passive"))
      (node (ref "R88") (pin "2") (pinfunction "2_2") (pintype "passive"))
      (node (ref "U8") (pin "8") (pinfunction "CLK0_-_8") (pintype "passive"))
    )
    (net (code "39") (name "Net-(U8-CLK1_+)") (class "Default")
      (node (ref "R89") (pin "1") (pinfunction "1_1") (pintype "passive"))
      (node (ref "U8") (pin "11") (pinfunction "CLK1_+_11") (pintype "passive"))
    )
    (net (code "40") (name "Net-(U8-CLK1_-)") (class "Default")
      (node (ref "R90") (pin "1") (pinfunction "1_1") (pintype "passive"))
      (node (ref "U8") (pin "12") (pinfunction "CLK1_-_12") (pintype "passive"))
    )
    (net (code "41") (name "Net-(U8-CLK_SEL)") (class "Default")
      (node (ref "R181") (pin "1") (pinfunction "1_1") (pintype "passive"))
      (node (ref "U8") (pin "13") (pinfunction "CLK_SEL_13") (pintype "passive"))
    )
    (net (code "42") (name "Net-(Y1-OUT)") (class "Default")
      (node (ref "R82") (pin "2") (pinfunction "2_2") (pintype "passive"))
      (node (ref "Y1") (pin "3") (pinfunction "OUT_3") (pintype "passive"))
    )
    (net (code "43") (name "unconnected-(U7-NC-Pad9)") (class "Default")
      (node (ref "U7") (pin "9") (pinfunction "NC_9") (pintype "passive+no_connect"))
    )
    (net (code "44") (name "unconnected-(U7-NC-Pad10)") (class "Default")
      (node (ref "U7") (pin "10") (pinfunction "NC_10") (pintype "passive+no_connect"))
    )
    (net (code "45") (name "unconnected-(U8-NC-Pad9)") (class "Default")
      (node (ref "U8") (pin "9") (pinfunction "NC_9") (pintype "passive+no_connect"))
    )
    (net (code "46") (name "unconnected-(U8-NC-Pad10)") (class "Default")
      (node (ref "U8") (pin "10") (pinfunction "NC_10") (pintype "passive+no_connect"))
    )
  )
)
